# Front_v1.net
KiCad netlist of a schematic drawn in EAGLE
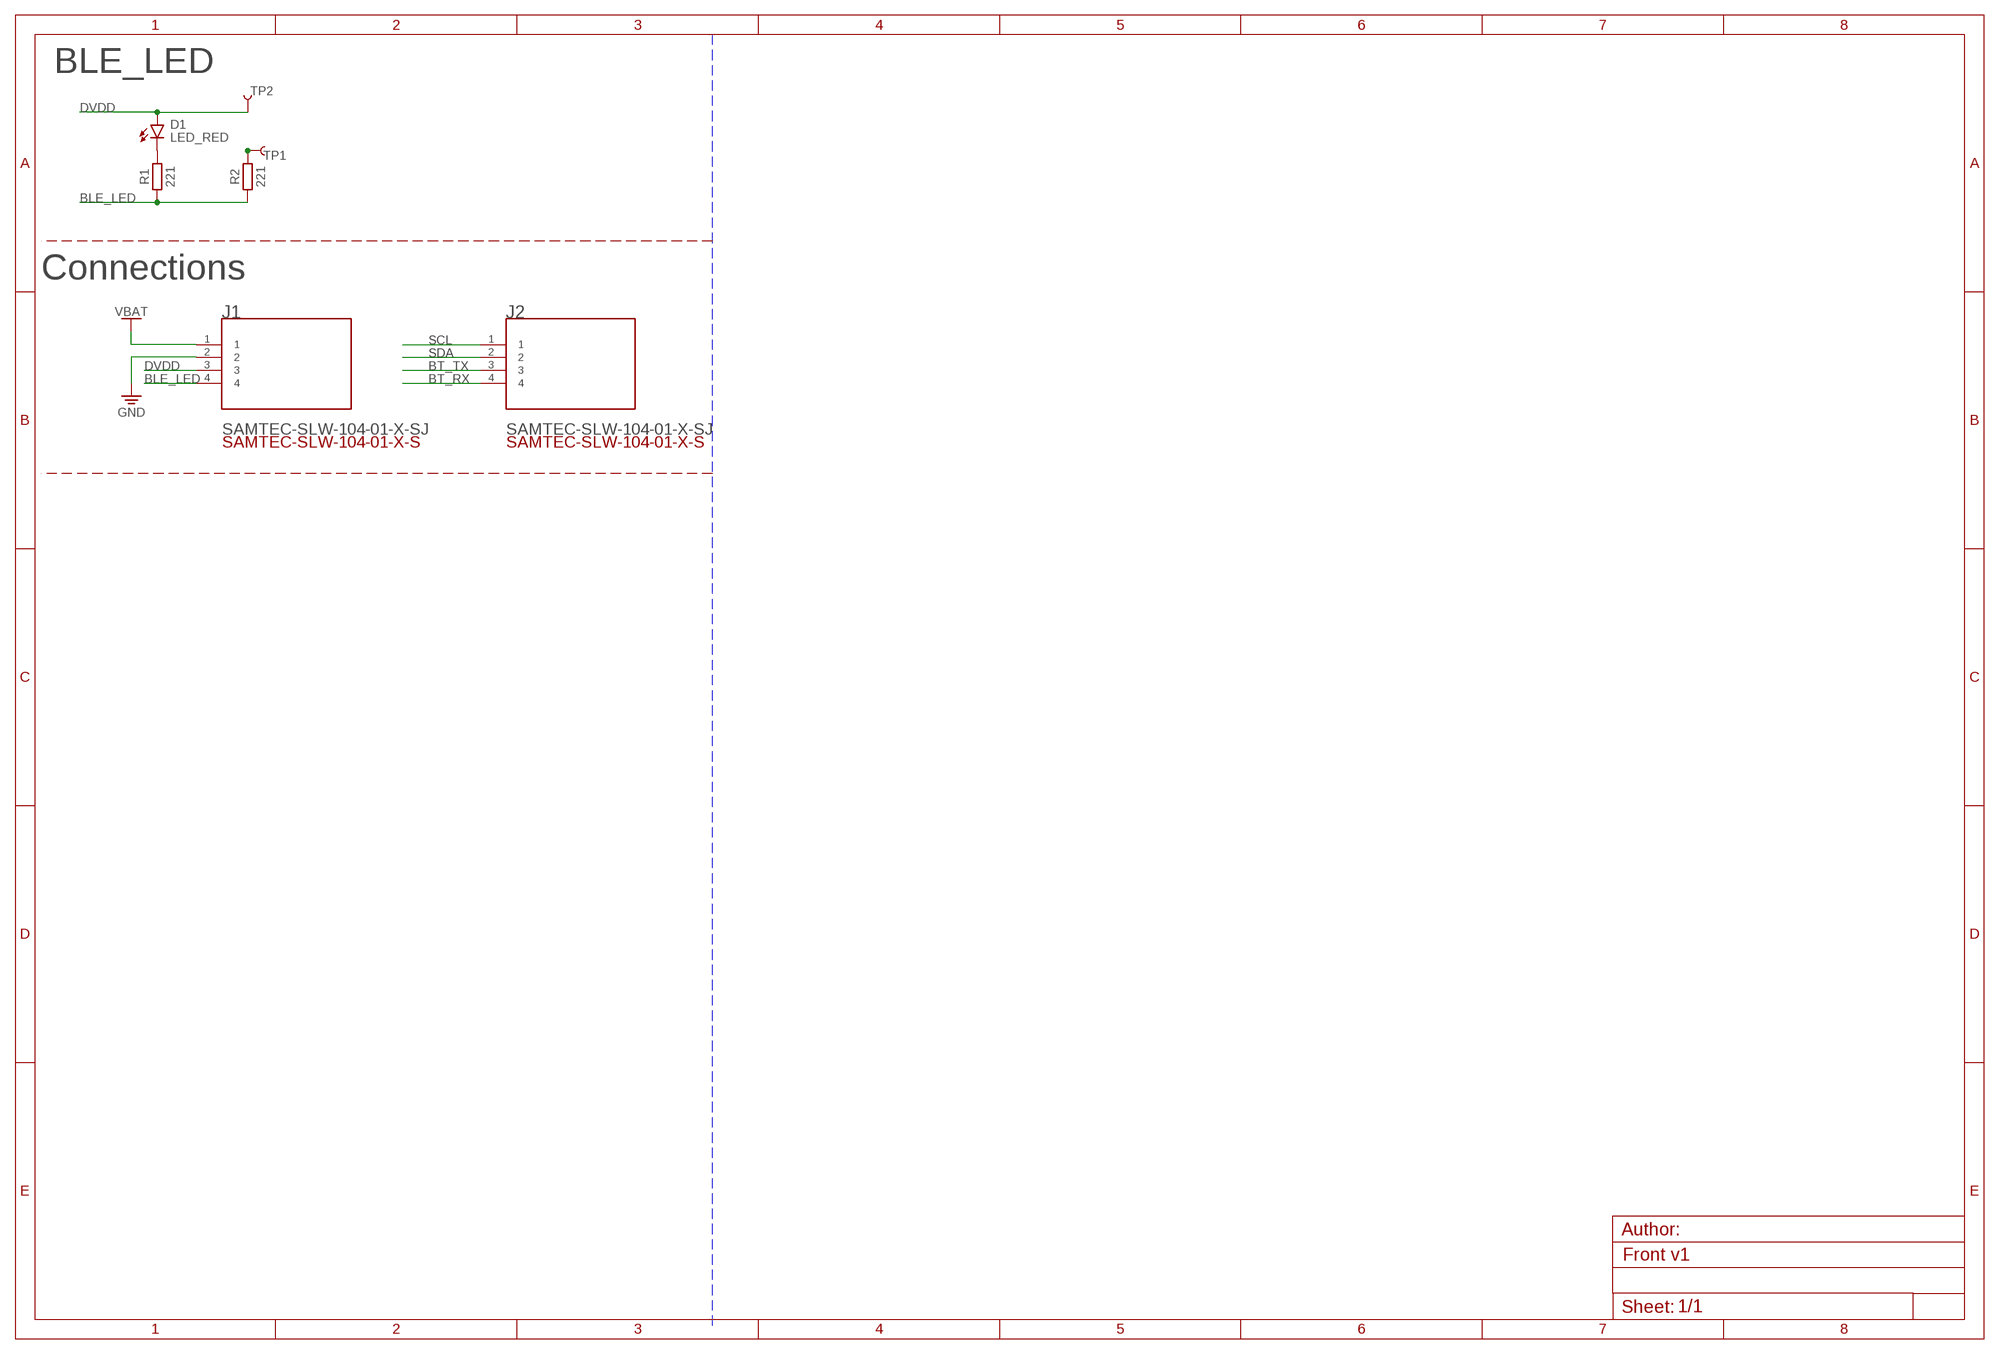
[diagram p0: schematic, sheet 1]

(export (version "E")
  (design (tool "Eeschema 10.0.6"))
  (components
    (comp (ref "D1")
      (value "LED_RED")
      (footprint "eagle-import:LEDC1608X65N_RND-R")
      (libsource (lib "eagle-import") (part "CHIP-ROUND-R_0603"))
    )
    (comp (ref "J1")
      (value "SAMTEC-SLW-104-01-X-SJ")
      (footprint "eagle-import:SAMTEC-SLW-104-01-X-S")
      (libsource (lib "eagle-import") (part "SAMTEC-SLW-104-01-X-SJ"))
    )
    (comp (ref "J2")
      (value "SAMTEC-SLW-104-01-X-SJ")
      (footprint "eagle-import:SAMTEC-SLW-104-01-X-S")
      (libsource (lib "eagle-import") (part "SAMTEC-SLW-104-01-X-SJ"))
    )
    (comp (ref "R1")
      (value "221")
      (footprint "eagle-import:RESC1608X60")
      (libsource (lib "eagle-import") (part "RCHIP-0603(1608-METRIC)_"))
    )
    (comp (ref "R2")
      (value "221")
      (footprint "eagle-import:RESC1608X60")
      (libsource (lib "eagle-import") (part "RCHIP-0603(1608-METRIC)_"))
    )
    (comp (ref "TP1")
      (value "TEST-POINT3X5")
      (footprint "eagle-import:PAD.03X.05")
      (libsource (lib "eagle-import") (part "TEST-POINT3X5"))
    )
    (comp (ref "TP2")
      (value "TEST-POINT3X5")
      (footprint "eagle-import:PAD.03X.05")
      (libsource (lib "eagle-import") (part "TEST-POINT3X5"))
    )
  )
  (nets
    (net (code "1") (name "/BLE_LED") (class "Default")
      (node (ref "J1") (pin "4") (pinfunction "4_4") (pintype "bidirectional"))
      (node (ref "R1") (pin "1") (pinfunction "1_1") (pintype "passive"))
      (node (ref "R2") (pin "1") (pinfunction "1_1") (pintype "passive"))
    )
    (net (code "2") (name "/BT_RX") (class "Default")
      (node (ref "J2") (pin "4") (pinfunction "4_4") (pintype "bidirectional"))
    )
    (net (code "3") (name "/BT_TX") (class "Default")
      (node (ref "J2") (pin "3") (pinfunction "3_3") (pintype "bidirectional"))
    )
    (net (code "4") (name "/DVDD") (class "Default")
      (node (ref "D1") (pin "A") (pinfunction "A_A") (pintype "passive"))
      (node (ref "J1") (pin "3") (pinfunction "3_3") (pintype "bidirectional"))
      (node (ref "TP2") (pin "P$1") (pinfunction "1_P$1") (pintype "bidirectional"))
    )
    (net (code "5") (name "/SCL") (class "Default")
      (node (ref "J2") (pin "1") (pinfunction "1_1") (pintype "bidirectional"))
    )
    (net (code "6") (name "/SDA") (class "Default")
      (node (ref "J2") (pin "2") (pinfunction "2_2") (pintype "bidirectional"))
    )
    (net (code "7") (name "GND") (class "Default")
      (node (ref "J1") (pin "2") (pinfunction "2_2") (pintype "bidirectional"))
    )
    (net (code "8") (name "Net-(D1-PadC)") (class "Default")
      (node (ref "D1") (pin "C") (pinfunction "C_C") (pintype "passive"))
      (node (ref "R1") (pin "2") (pinfunction "2_2") (pintype "passive"))
    )
    (net (code "9") (name "Net-(TP1-1)") (class "Default")
      (node (ref "R2") (pin "2") (pinfunction "2_2") (pintype "passive"))
      (node (ref "TP1") (pin "P$1") (pinfunction "1_P$1") (pintype "bidirectional"))
    )
    (net (code "10") (name "VBAT") (class "Default")
      (node (ref "J1") (pin "1") (pinfunction "1_1") (pintype "bidirectional"))
    )
  )
)
